# MB1-Pwr-r1_0.net
KiCad netlist of a schematic drawn in Altium Designer
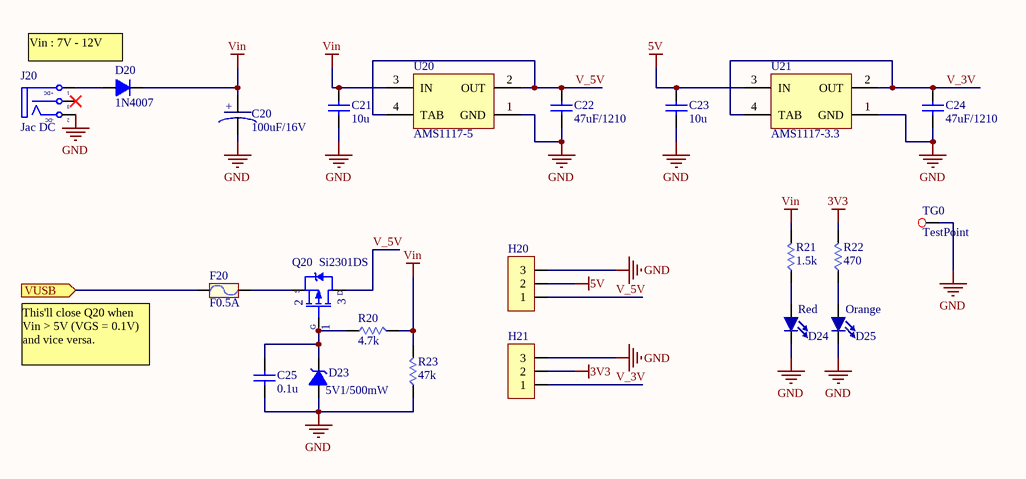
[diagram p0: MB1-Pwr-r1.0.SchDoc]

(export (version "E")
  (design (tool "Eeschema 10.0.6"))
  (components
    (comp (ref "C20")
      (value "100uF/16V")
      (footprint "TantalumCaseD")
      (fields (field (name "Comment") "CapT"))
      (libsource (lib "MyLib") (part "CapA"))
    )
    (comp (ref "C21")
      (value "10u")
      (footprint "SM_0805_LD")
      (description "Non-polarity ceramic capacitor")
      (fields (field (name "Comment") "CAP Ceramic") (field (name "PUBLISHER") "Altium Limited"))
      (libsource (lib "HLib_schematic_lib") (part "CAP Ceramic"))
    )
    (comp (ref "C22")
      (value "47uF/1210")
      (footprint "SM-1210")
      (description "Non-polarity ceramic capacitor")
      (fields (field (name "Comment") "CAP Ceramic") (field (name "PUBLISHER") "Altium Limited"))
      (libsource (lib "HLib_schematic_lib") (part "CAP Ceramic"))
    )
    (comp (ref "C23")
      (value "10u")
      (footprint "SM_0805_LD")
      (description "Non-polarity ceramic capacitor")
      (fields (field (name "Comment") "CAP Ceramic") (field (name "PUBLISHER") "Altium Limited"))
      (libsource (lib "HLib_schematic_lib") (part "CAP Ceramic"))
    )
    (comp (ref "C24")
      (value "47uF/1210")
      (footprint "SM-1210")
      (description "Non-polarity ceramic capacitor")
      (fields (field (name "Comment") "CAP Ceramic") (field (name "PUBLISHER") "Altium Limited"))
      (libsource (lib "HLib_schematic_lib") (part "CAP Ceramic"))
    )
    (comp (ref "C25")
      (value "0.1u")
      (footprint "SM_0805_LD")
      (description "Non-polarity ceramic capacitor")
      (fields (field (name "Comment") "CAP Ceramic") (field (name "PUBLISHER") "Altium Limited"))
      (libsource (lib "HLib_schematic_lib") (part "CAP Ceramic"))
    )
    (comp (ref "D20")
      (value "1N4007")
      (footprint "DO-214AC")
      (description "Diode 1A")
      (libsource (lib "VioletofSun") (part "D1A"))
    )
    (comp (ref "D23")
      (value "5V1/500mW")
      (footprint "SOD-123")
      (description "Diode Zenner")
      (libsource (lib "VioletofSun") (part "DZ"))
    )
    (comp (ref "D24")
      (value "Red")
      (footprint "SM_0805_POL_LD")
      (description "LED")
      (fields (field (name "PUBLISHER") "Altium Limited"))
      (libsource (lib "HLib_schematic_lib") (part "LED"))
    )
    (comp (ref "D25")
      (value "Orange")
      (footprint "SM_0805_POL_LD")
      (description "LED")
      (fields (field (name "PUBLISHER") "Altium Limited"))
      (libsource (lib "HLib_schematic_lib") (part "LED"))
    )
    (comp (ref "F20")
      (value "F0.5A")
      (footprint "SMD-1812")
      (description "Fuse")
      (fields (field (name "DESIGNED BY") "VanDungEvn"))
      (libsource (lib "VioletofSun") (part "Fuse"))
    )
    (comp (ref "H20") (value "Hed3") (footprint "Hed3") (libsource (lib "MyLib") (part "Hed3")))
    (comp (ref "H21") (value "Hed3") (footprint "Hed3") (libsource (lib "MyLib") (part "Hed3")))
    (comp (ref "J20")
      (value "Jac DC")
      (footprint "DCJack")
      (description "Jac DC input")
      (libsource (lib "VioletofSun") (part "DCIN"))
    )
    (comp (ref "Q20")
      (value "Si2301DS")
      (footprint "SOT23")
      (description "P-Channel 1.25-W, 2.5-V MOSFET")
      (libsource (lib "MyLib") (part "P-MOSFET"))
    )
    (comp (ref "R20")
      (value "4.7k")
      (footprint "SM_0805_LD")
      (description "Resistor")
      (fields (field (name "PUBLISHER") "Altium Limited"))
      (libsource (lib "HLib_schematic_lib") (part "R"))
    )
    (comp (ref "R21")
      (value "1.5k")
      (footprint "SM_0805_LD")
      (description "Resistor")
      (fields (field (name "PUBLISHER") "Altium Limited"))
      (libsource (lib "HLib_schematic_lib") (part "R"))
    )
    (comp (ref "R22")
      (value "470")
      (footprint "SM_0805_LD")
      (description "Resistor")
      (fields (field (name "PUBLISHER") "Altium Limited"))
      (libsource (lib "HLib_schematic_lib") (part "R"))
    )
    (comp (ref "R23")
      (value "47k")
      (footprint "SM_0805_LD")
      (description "Resistor")
      (fields (field (name "PUBLISHER") "Altium Limited"))
      (libsource (lib "HLib_schematic_lib") (part "R"))
    )
    (comp (ref "TG0")
      (value "TestPoint")
      (footprint "TestPoint")
      (libsource (lib "MyLib") (part "TestPoint"))
    )
    (comp (ref "U20")
      (value "AMS1117-5")
      (footprint "MP04A_N")
      (description "800mA Low-Dropout Linear Regulator, 4-pin SOT-223")
      (fields
        (field (name "PARTNUMBER") "LM1117IMP-3.3")
        (field (name "MANUFACTURER") "National Semiconductor")
        (field (name "PUBLISHER") "Altium Limited")
      )
      (libsource (lib "NSC LDO") (part "LM1117IMP-3.3"))
    )
    (comp (ref "U21")
      (value "AMS1117-3.3")
      (footprint "MP04A_N")
      (description "800mA Low-Dropout Linear Regulator, 4-pin SOT-223")
      (fields
        (field (name "PARTNUMBER") "LM1117IMP-3.3")
        (field (name "MANUFACTURER") "National Semiconductor")
        (field (name "PUBLISHER") "Altium Limited")
      )
      (libsource (lib "NSC LDO") (part "LM1117IMP-3.3"))
    )
  )
  (nets
    (net (code "1") (name "/VUSB") (class "Default")
      (node (ref "F20") (pin "1") (pinfunction "1_1") (pintype "passive"))
    )
    (net (code "2") (name "/V_3V") (class "Default")
      (node (ref "C24") (pin "2") (pinfunction "2_2") (pintype "passive"))
      (node (ref "H21") (pin "1") (pinfunction "1_1") (pintype "passive"))
      (node (ref "U21") (pin "2") (pinfunction "OUT_2") (pintype "power_in"))
      (node (ref "U21") (pin "4") (pinfunction "TAB_4") (pintype "power_in"))
    )
    (net (code "3") (name "/V_5V") (class "Default")
      (node (ref "C22") (pin "2") (pinfunction "2_2") (pintype "passive"))
      (node (ref "H20") (pin "1") (pinfunction "1_1") (pintype "passive"))
      (node (ref "Q20") (pin "3") (pinfunction "D_3") (pintype "passive"))
      (node (ref "U20") (pin "2") (pinfunction "OUT_2") (pintype "power_in"))
      (node (ref "U20") (pin "4") (pinfunction "TAB_4") (pintype "power_in"))
    )
    (net (code "4") (name "3V3") (class "Default")
      (node (ref "H21") (pin "2") (pinfunction "2_2") (pintype "passive"))
      (node (ref "R22") (pin "2") (pinfunction "2_2") (pintype "passive"))
    )
    (net (code "5") (name "5V") (class "Default")
      (node (ref "C23") (pin "2") (pinfunction "2_2") (pintype "passive"))
      (node (ref "H20") (pin "2") (pinfunction "2_2") (pintype "passive"))
      (node (ref "U21") (pin "3") (pinfunction "IN_3") (pintype "power_in"))
    )
    (net (code "6") (name "GND") (class "Default")
      (node (ref "C20") (pin "2") (pinfunction "-_2") (pintype "passive"))
      (node (ref "C21") (pin "1") (pinfunction "1_1") (pintype "passive"))
      (node (ref "C22") (pin "1") (pinfunction "1_1") (pintype "passive"))
      (node (ref "C23") (pin "1") (pinfunction "1_1") (pintype "passive"))
      (node (ref "C24") (pin "1") (pinfunction "1_1") (pintype "passive"))
      (node (ref "C25") (pin "1") (pinfunction "1_1") (pintype "passive"))
      (node (ref "D23") (pin "1") (pinfunction "A_1") (pintype "passive"))
      (node (ref "D24") (pin "2") (pinfunction "K_2") (pintype "passive"))
      (node (ref "D25") (pin "2") (pinfunction "K_2") (pintype "passive"))
      (node (ref "H20") (pin "3") (pinfunction "3_3") (pintype "passive"))
      (node (ref "H21") (pin "3") (pinfunction "3_3") (pintype "passive"))
      (node (ref "J20") (pin "2") (pinfunction "TN_2") (pintype "passive"))
      (node (ref "R23") (pin "1") (pinfunction "1_1") (pintype "passive"))
      (node (ref "TG0") (pin "1") (pinfunction "0_1") (pintype "passive"))
      (node (ref "U20") (pin "1") (pinfunction "GND_1") (pintype "power_in"))
      (node (ref "U21") (pin "1") (pinfunction "GND_1") (pintype "power_in"))
    )
    (net (code "7") (name "Net-(D20-A)") (class "Default")
      (node (ref "D20") (pin "1") (pinfunction "A_1") (pintype "passive"))
      (node (ref "J20") (pin "1") (pinfunction "T_1") (pintype "passive"))
    )
    (net (code "8") (name "Net-(D23-K)") (class "Default")
      (node (ref "C25") (pin "2") (pinfunction "2_2") (pintype "passive"))
      (node (ref "D23") (pin "2") (pinfunction "K_2") (pintype "passive"))
      (node (ref "Q20") (pin "1") (pinfunction "G_1") (pintype "passive"))
      (node (ref "R20") (pin "1") (pinfunction "1_1") (pintype "passive"))
    )
    (net (code "9") (name "Net-(D24-A)") (class "Default")
      (node (ref "D24") (pin "1") (pinfunction "A_1") (pintype "passive"))
      (node (ref "R21") (pin "1") (pinfunction "1_1") (pintype "passive"))
    )
    (net (code "10") (name "Net-(D25-A)") (class "Default")
      (node (ref "D25") (pin "1") (pinfunction "A_1") (pintype "passive"))
      (node (ref "R22") (pin "1") (pinfunction "1_1") (pintype "passive"))
    )
    (net (code "11") (name "Net-(Q20-S)") (class "Default")
      (node (ref "F20") (pin "2") (pinfunction "2_2") (pintype "passive"))
      (node (ref "Q20") (pin "2") (pinfunction "S_2") (pintype "passive"))
    )
    (net (code "12") (name "Vin") (class "Default")
      (node (ref "C20") (pin "1") (pinfunction "+_1") (pintype "passive"))
      (node (ref "C21") (pin "2") (pinfunction "2_2") (pintype "passive"))
      (node (ref "D20") (pin "2") (pinfunction "K_2") (pintype "passive"))
      (node (ref "R20") (pin "2") (pinfunction "2_2") (pintype "passive"))
      (node (ref "R21") (pin "2") (pinfunction "2_2") (pintype "passive"))
      (node (ref "R23") (pin "2") (pinfunction "2_2") (pintype "passive"))
      (node (ref "U20") (pin "3") (pinfunction "IN_3") (pintype "power_in"))
    )
    (net (code "13") (name "unconnected-(J20-S-Pad3)") (class "Default")
      (node (ref "J20") (pin "3") (pinfunction "S_3") (pintype "power_in+no_connect"))
    )
  )
)
